# LB-char-topLevel.net
KiCad netlist of a schematic drawn in Altium Designer
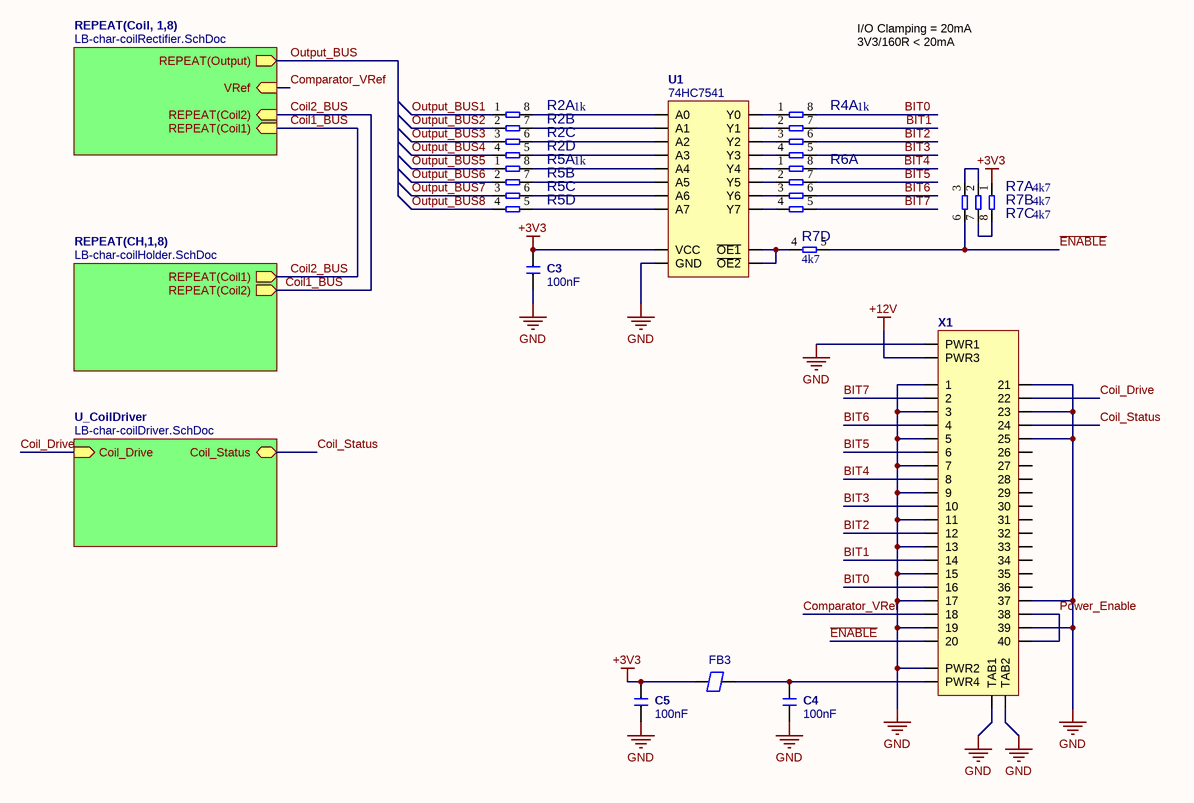
[diagram p0: LB-char-topLevel.SchDoc]

(export (version "E")
  (design (tool "Eeschema 10.0.6"))
  (components
    (comp (ref "C3")
      (value "100nF")
      (footprint "C0603_N")
      (description "Capacitor MLCC")
      (fields
        (field (name "MANUFACTURER") "Yageo")
        (field (name "MANUFACTURER PART NUMBER") "CC0603KRX7R9BB104")
      )
      (libsource (lib "wes") (part "Capacitor"))
    )
    (comp (ref "C4")
      (value "100nF")
      (footprint "C0603_N")
      (description "Capacitor MLCC")
      (fields
        (field (name "MANUFACTURER") "Yageo")
        (field (name "MANUFACTURER PART NUMBER") "CC0603KRX7R9BB104")
      )
      (libsource (lib "wes") (part "Capacitor"))
    )
    (comp (ref "C5")
      (value "100nF")
      (footprint "C0603_N")
      (description "Capacitor MLCC")
      (fields
        (field (name "MANUFACTURER") "Yageo")
        (field (name "MANUFACTURER PART NUMBER") "CC0603KRX7R9BB104")
      )
      (libsource (lib "wes") (part "Capacitor"))
    )
    (comp (ref "FB3") (value "FB") (footprint "F0603_N") (libsource (lib "wes") (part "Ferrite Bead")))
    (comp (ref "R2")
      (value "1k")
      (footprint "YC164")
      (fields (field (name "Comment") "; 1k"))
      (libsource (lib "wes") (part "Resistor Array - 4P"))
    )
    (comp (ref "R4")
      (value "1k")
      (footprint "YC164")
      (fields (field (name "Comment") "; 1k"))
      (libsource (lib "wes") (part "Resistor Array - 4P"))
    )
    (comp (ref "R5") (value "; 1k") (footprint "YC164") (libsource (lib "wes") (part "Resistor Array - 4P")))
    (comp (ref "R6") (value "; 1k") (footprint "YC164") (libsource (lib "wes") (part "Resistor Array - 4P")))
    (comp (ref "R7")
      (value "4k7")
      (footprint "YC164")
      (fields (field (name "Comment") "; 4k7"))
      (libsource (lib "wes") (part "Resistor Array - 4P"))
    )
    (comp (ref "U1")
      (value "74HC7541")
      (footprint "TSSOP20_N")
      (description "Schmitt Trigger Octal")
      (libsource (lib "wes") (part "74HC7541"))
    )
    (comp (ref "X1")
      (value "FX23 Right Angle Receptacle")
      (footprint "FX23-40S-0.5SH")
      (description "FX23 Right Angle Receptacle 40 Pos")
      (libsource (lib "wes") (part "FX23-40S-0.5SH"))
    )
  )
  (nets
    (net (code "1") (name "+3V3") (class "Default")
      (node (ref "C3") (pin "1") (pintype "passive"))
      (node (ref "C5") (pin "1") (pintype "passive"))
      (node (ref "FB3") (pin "2") (pinfunction "2_2") (pintype "passive"))
      (node (ref "R7") (pin "1") (pinfunction "1_1") (pintype "passive"))
      (node (ref "U1") (pin "20") (pinfunction "VCC_20") (pintype "passive"))
    )
    (net (code "2") (name "+12V") (class "Default")
      (node (ref "X1") (pin "PWR3") (pinfunction "PWR3_PWR3") (pintype "power_in"))
    )
    (net (code "3") (name "/BIT0") (class "Default")
      (node (ref "R4") (pin "8") (pinfunction "8_8") (pintype "passive"))
      (node (ref "X1") (pin "16") (pinfunction "16_16") (pintype "power_in"))
    )
    (net (code "4") (name "/BIT1") (class "Default")
      (node (ref "R4") (pin "7") (pinfunction "7_7") (pintype "passive"))
      (node (ref "X1") (pin "14") (pinfunction "14_14") (pintype "power_in"))
    )
    (net (code "5") (name "/BIT2") (class "Default")
      (node (ref "R4") (pin "6") (pinfunction "6_6") (pintype "passive"))
      (node (ref "X1") (pin "12") (pinfunction "12_12") (pintype "power_in"))
    )
    (net (code "6") (name "/BIT3") (class "Default")
      (node (ref "R4") (pin "5") (pinfunction "5_5") (pintype "passive"))
      (node (ref "X1") (pin "10") (pinfunction "10_10") (pintype "power_in"))
    )
    (net (code "7") (name "/BIT4") (class "Default")
      (node (ref "R6") (pin "8") (pinfunction "8_8") (pintype "passive"))
      (node (ref "X1") (pin "8") (pinfunction "8_8") (pintype "power_in"))
    )
    (net (code "8") (name "/BIT5") (class "Default")
      (node (ref "R6") (pin "7") (pinfunction "7_7") (pintype "passive"))
      (node (ref "X1") (pin "6") (pinfunction "6_6") (pintype "power_in"))
    )
    (net (code "9") (name "/BIT6") (class "Default")
      (node (ref "R6") (pin "6") (pinfunction "6_6") (pintype "passive"))
      (node (ref "X1") (pin "4") (pinfunction "4_4") (pintype "power_in"))
    )
    (net (code "10") (name "/BIT7") (class "Default")
      (node (ref "R6") (pin "5") (pinfunction "5_5") (pintype "passive"))
      (node (ref "X1") (pin "2") (pinfunction "2_2") (pintype "power_in"))
    )
    (net (code "13") (name "/Coil_Drive") (class "Default")
      (node (ref "X1") (pin "22") (pinfunction "22_22") (pintype "power_in"))
    )
    (net (code "14") (name "/Coil_Status") (class "Default")
      (node (ref "X1") (pin "24") (pinfunction "24_24") (pintype "power_in"))
    )
    (net (code "15") (name "/Comparator_VRef") (class "Default")
      (node (ref "X1") (pin "18") (pinfunction "18_18") (pintype "power_in"))
    )
    (net (code "17") (name "/Output_BUS1") (class "Default")
      (node (ref "R2") (pin "1") (pinfunction "1_1") (pintype "passive"))
    )
    (net (code "18") (name "/Output_BUS2") (class "Default")
      (node (ref "R2") (pin "2") (pinfunction "2_2") (pintype "passive"))
    )
    (net (code "19") (name "/Output_BUS3") (class "Default")
      (node (ref "R2") (pin "3") (pinfunction "3_3") (pintype "passive"))
    )
    (net (code "20") (name "/Output_BUS4") (class "Default")
      (node (ref "R2") (pin "4") (pinfunction "4_4") (pintype "passive"))
    )
    (net (code "21") (name "/Output_BUS5") (class "Default")
      (node (ref "R5") (pin "1") (pinfunction "1_1") (pintype "passive"))
    )
    (net (code "22") (name "/Output_BUS6") (class "Default")
      (node (ref "R5") (pin "2") (pinfunction "2_2") (pintype "passive"))
    )
    (net (code "23") (name "/Output_BUS7") (class "Default")
      (node (ref "R5") (pin "3") (pinfunction "3_3") (pintype "passive"))
    )
    (net (code "24") (name "/Output_BUS8") (class "Default")
      (node (ref "R5") (pin "4") (pinfunction "4_4") (pintype "passive"))
    )
    (net (code "25") (name "/Power_Enable") (class "Default")
      (node (ref "X1") (pin "38") (pinfunction "38_38") (pintype "power_in"))
      (node (ref "X1") (pin "40") (pinfunction "40_40") (pintype "power_in"))
    )
    (net (code "26") (name "/~{ENABLE}") (class "Default")
      (node (ref "R7") (pin "5") (pinfunction "5_5") (pintype "passive"))
      (node (ref "R7") (pin "6") (pinfunction "6_6") (pintype "passive"))
      (node (ref "X1") (pin "20") (pinfunction "20_20") (pintype "power_in"))
    )
    (net (code "27") (name "GND") (class "Default")
      (node (ref "C3") (pin "2") (pintype "passive"))
      (node (ref "C4") (pin "2") (pintype "passive"))
      (node (ref "C5") (pin "2") (pintype "passive"))
      (node (ref "U1") (pin "10") (pinfunction "GND_10") (pintype "passive"))
      (node (ref "X1") (pin "1") (pinfunction "1_1") (pintype "power_in"))
      (node (ref "X1") (pin "11") (pinfunction "11_11") (pintype "power_in"))
      (node (ref "X1") (pin "13") (pinfunction "13_13") (pintype "power_in"))
      (node (ref "X1") (pin "15") (pinfunction "15_15") (pintype "power_in"))
      (node (ref "X1") (pin "17") (pinfunction "17_17") (pintype "power_in"))
      (node (ref "X1") (pin "19") (pinfunction "19_19") (pintype "power_in"))
      (node (ref "X1") (pin "21") (pinfunction "21_21") (pintype "power_in"))
      (node (ref "X1") (pin "23") (pinfunction "23_23") (pintype "power_in"))
      (node (ref "X1") (pin "25") (pinfunction "25_25") (pintype "power_in"))
      (node (ref "X1") (pin "3") (pinfunction "3_3") (pintype "power_in"))
      (node (ref "X1") (pin "37") (pinfunction "37_37") (pintype "power_in"))
      (node (ref "X1") (pin "39") (pinfunction "39_39") (pintype "power_in"))
      (node (ref "X1") (pin "5") (pinfunction "5_5") (pintype "power_in"))
      (node (ref "X1") (pin "7") (pinfunction "7_7") (pintype "power_in"))
      (node (ref "X1") (pin "9") (pinfunction "9_9") (pintype "power_in"))
      (node (ref "X1") (pin "PWR1") (pinfunction "PWR1_PWR1") (pintype "power_in"))
      (node (ref "X1") (pin "PWR2") (pinfunction "PWR2_PWR2") (pintype "power_in"))
      (node (ref "X1") (pin "TAB1") (pinfunction "TAB1_TAB1") (pintype "power_in"))
      (node (ref "X1") (pin "TAB2") (pinfunction "TAB2_TAB2") (pintype "power_in"))
    )
    (net (code "28") (name "Net-(C4-Pad1)") (class "Default")
      (node (ref "C4") (pin "1") (pintype "passive"))
      (node (ref "FB3") (pin "1") (pinfunction "1_1") (pintype "passive"))
      (node (ref "X1") (pin "PWR4") (pinfunction "PWR4_PWR4") (pintype "power_in"))
    )
    (net (code "29") (name "Net-(R7-Pad2)") (class "Default")
      (node (ref "R7") (pin "2") (pinfunction "2_2") (pintype "passive"))
      (node (ref "R7") (pin "3") (pinfunction "3_3") (pintype "passive"))
    )
    (net (code "30") (name "Net-(R7-Pad7)") (class "Default")
      (node (ref "R7") (pin "7") (pinfunction "7_7") (pintype "passive"))
      (node (ref "R7") (pin "8") (pinfunction "8_8") (pintype "passive"))
    )
    (net (code "31") (name "Net-(U1-A0)") (class "Default")
      (node (ref "R2") (pin "8") (pinfunction "8_8") (pintype "passive"))
      (node (ref "U1") (pin "2") (pinfunction "A0_2") (pintype "passive"))
    )
    (net (code "32") (name "Net-(U1-A1)") (class "Default")
      (node (ref "R2") (pin "7") (pinfunction "7_7") (pintype "passive"))
      (node (ref "U1") (pin "3") (pinfunction "A1_3") (pintype "passive"))
    )
    (net (code "33") (name "Net-(U1-A2)") (class "Default")
      (node (ref "R2") (pin "6") (pinfunction "6_6") (pintype "passive"))
      (node (ref "U1") (pin "4") (pinfunction "A2_4") (pintype "passive"))
    )
    (net (code "34") (name "Net-(U1-A3)") (class "Default")
      (node (ref "R2") (pin "5") (pinfunction "5_5") (pintype "passive"))
      (node (ref "U1") (pin "5") (pinfunction "A3_5") (pintype "passive"))
    )
    (net (code "35") (name "Net-(U1-A4)") (class "Default")
      (node (ref "R5") (pin "8") (pinfunction "8_8") (pintype "passive"))
      (node (ref "U1") (pin "6") (pinfunction "A4_6") (pintype "passive"))
    )
    (net (code "36") (name "Net-(U1-A5)") (class "Default")
      (node (ref "R5") (pin "7") (pinfunction "7_7") (pintype "passive"))
      (node (ref "U1") (pin "7") (pinfunction "A5_7") (pintype "passive"))
    )
    (net (code "37") (name "Net-(U1-A6)") (class "Default")
      (node (ref "R5") (pin "6") (pinfunction "6_6") (pintype "passive"))
      (node (ref "U1") (pin "8") (pinfunction "A6_8") (pintype "passive"))
    )
    (net (code "38") (name "Net-(U1-A7)") (class "Default")
      (node (ref "R5") (pin "5") (pinfunction "5_5") (pintype "passive"))
      (node (ref "U1") (pin "9") (pinfunction "A7_9") (pintype "passive"))
    )
    (net (code "39") (name "Net-(U1-Y0)") (class "Default")
      (node (ref "R4") (pin "1") (pinfunction "1_1") (pintype "passive"))
      (node (ref "U1") (pin "18") (pinfunction "Y0_18") (pintype "passive"))
    )
    (net (code "40") (name "Net-(U1-Y1)") (class "Default")
      (node (ref "R4") (pin "2") (pinfunction "2_2") (pintype "passive"))
      (node (ref "U1") (pin "17") (pinfunction "Y1_17") (pintype "passive"))
    )
    (net (code "41") (name "Net-(U1-Y2)") (class "Default")
      (node (ref "R4") (pin "3") (pinfunction "3_3") (pintype "passive"))
      (node (ref "U1") (pin "16") (pinfunction "Y2_16") (pintype "passive"))
    )
    (net (code "42") (name "Net-(U1-Y3)") (class "Default")
      (node (ref "R4") (pin "4") (pinfunction "4_4") (pintype "passive"))
      (node (ref "U1") (pin "15") (pinfunction "Y3_15") (pintype "passive"))
    )
    (net (code "43") (name "Net-(U1-Y4)") (class "Default")
      (node (ref "R6") (pin "1") (pinfunction "1_1") (pintype "passive"))
      (node (ref "U1") (pin "14") (pinfunction "Y4_14") (pintype "passive"))
    )
    (net (code "44") (name "Net-(U1-Y5)") (class "Default")
      (node (ref "R6") (pin "2") (pinfunction "2_2") (pintype "passive"))
      (node (ref "U1") (pin "13") (pinfunction "Y5_13") (pintype "passive"))
    )
    (net (code "45") (name "Net-(U1-Y6)") (class "Default")
      (node (ref "R6") (pin "3") (pinfunction "3_3") (pintype "passive"))
      (node (ref "U1") (pin "12") (pinfunction "Y6_12") (pintype "passive"))
    )
    (net (code "46") (name "Net-(U1-Y7)") (class "Default")
      (node (ref "R6") (pin "4") (pinfunction "4_4") (pintype "passive"))
      (node (ref "U1") (pin "11") (pinfunction "Y7_11") (pintype "passive"))
    )
    (net (code "47") (name "Net-(U1-~{OE1})") (class "Default")
      (node (ref "R7") (pin "4") (pinfunction "4_4") (pintype "passive"))
      (node (ref "U1") (pin "1") (pinfunction "~{OE1}_1") (pintype "passive"))
      (node (ref "U1") (pin "19") (pinfunction "~{OE2}_19") (pintype "passive"))
    )
    (net (code "48") (name "unconnected-(X1-Pad26)") (class "Default")
      (node (ref "X1") (pin "26") (pinfunction "26_26") (pintype "power_in"))
    )
    (net (code "49") (name "unconnected-(X1-Pad27)") (class "Default")
      (node (ref "X1") (pin "27") (pinfunction "27_27") (pintype "power_in"))
    )
    (net (code "50") (name "unconnected-(X1-Pad28)") (class "Default")
      (node (ref "X1") (pin "28") (pinfunction "28_28") (pintype "power_in"))
    )
    (net (code "51") (name "unconnected-(X1-Pad29)") (class "Default")
      (node (ref "X1") (pin "29") (pinfunction "29_29") (pintype "power_in"))
    )
    (net (code "52") (name "unconnected-(X1-Pad30)") (class "Default")
      (node (ref "X1") (pin "30") (pinfunction "30_30") (pintype "power_in"))
    )
    (net (code "53") (name "unconnected-(X1-Pad31)") (class "Default")
      (node (ref "X1") (pin "31") (pinfunction "31_31") (pintype "power_in"))
    )
    (net (code "54") (name "unconnected-(X1-Pad32)") (class "Default")
      (node (ref "X1") (pin "32") (pinfunction "32_32") (pintype "power_in"))
    )
    (net (code "55") (name "unconnected-(X1-Pad33)") (class "Default")
      (node (ref "X1") (pin "33") (pinfunction "33_33") (pintype "power_in"))
    )
    (net (code "56") (name "unconnected-(X1-Pad34)") (class "Default")
      (node (ref "X1") (pin "34") (pinfunction "34_34") (pintype "power_in"))
    )
    (net (code "57") (name "unconnected-(X1-Pad35)") (class "Default")
      (node (ref "X1") (pin "35") (pinfunction "35_35") (pintype "power_in"))
    )
    (net (code "58") (name "unconnected-(X1-Pad36)") (class "Default")
      (node (ref "X1") (pin "36") (pinfunction "36_36") (pintype "power_in"))
    )
  )
)
